# Item.net
KiCad netlist of a schematic drawn in Altium Designer
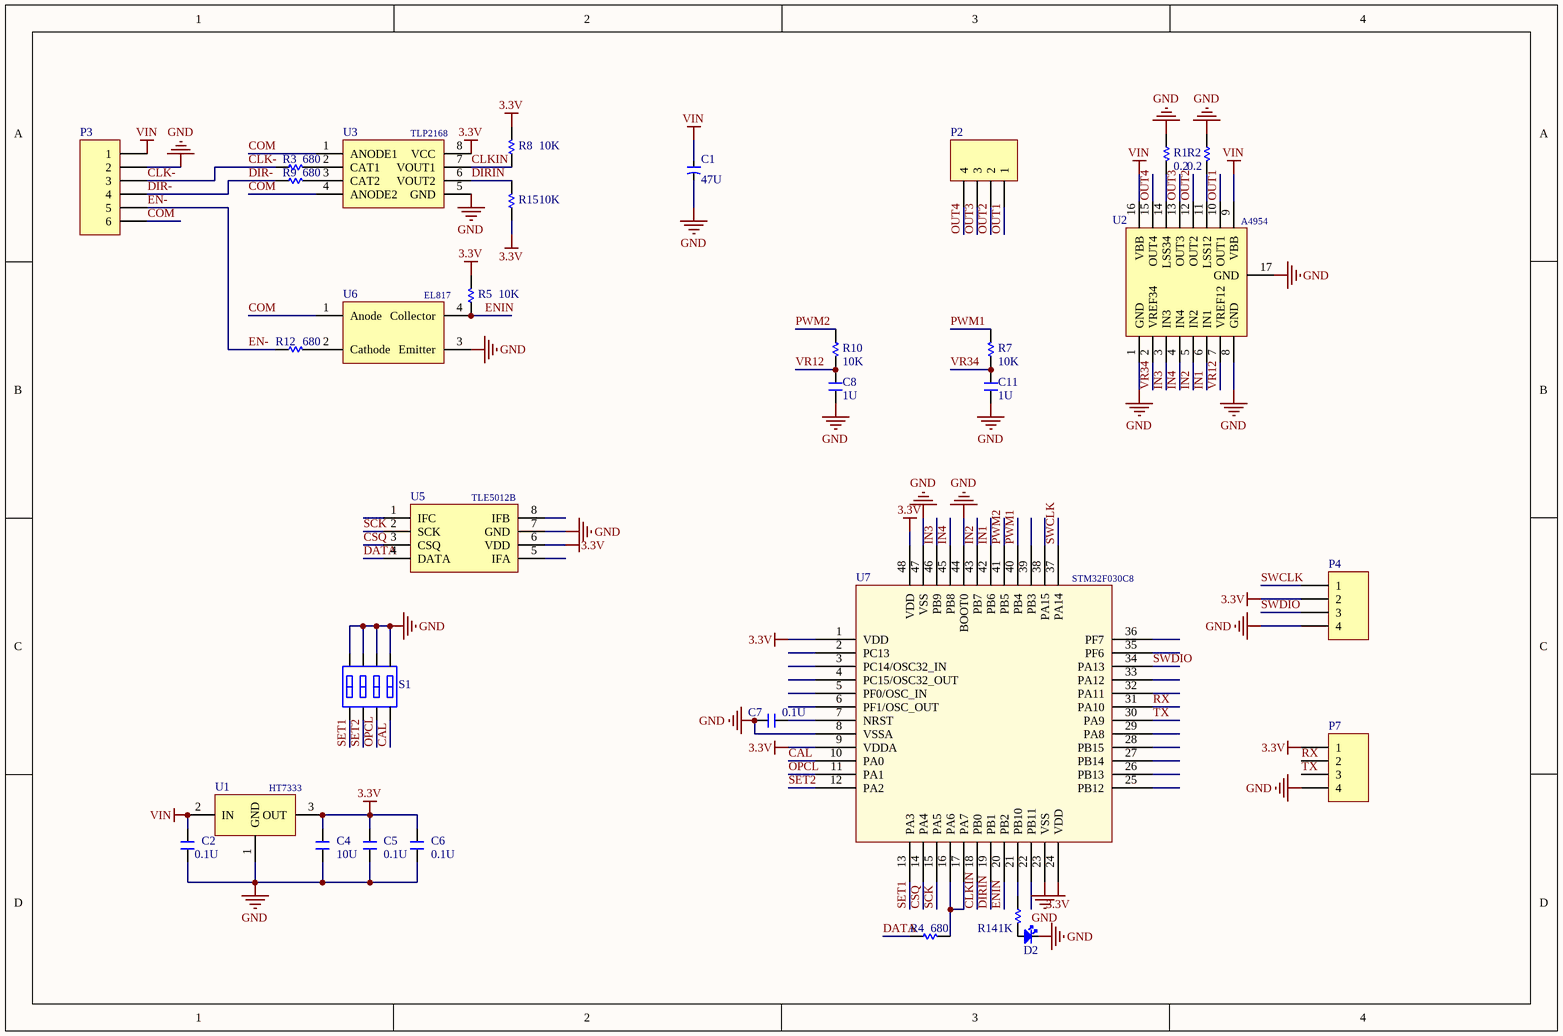
[diagram p0: Item.SchDoc]

(export (version "E")
  (design (tool "Eeschema 10.0.6"))
  (components
    (comp (ref "C1")
      (value "47U")
      (footprint "CAP6377")
      (description "Polarized Capacitor (Axial)")
      (fields (field (name "Comment") "CAP POL") (field (name "PUBLISHER") "Altium Limited"))
      (libsource (lib "MySchib") (part "CAP POL"))
    )
    (comp (ref "C2")
      (value "0.1U")
      (footprint "0805")
      (description "Capacitor")
      (fields (field (name "Comment") "CAP") (field (name "PUBLISHER") "Altium Limited"))
      (libsource (lib "MySchib") (part "CAP"))
    )
    (comp (ref "C4")
      (value "10U")
      (footprint "0805")
      (description "Capacitor")
      (fields (field (name "Comment") "CAP") (field (name "PUBLISHER") "Altium Limited"))
      (libsource (lib "MySchib") (part "CAP"))
    )
    (comp (ref "C5")
      (value "0.1U")
      (footprint "0805")
      (description "Capacitor")
      (fields (field (name "Comment") "CAP") (field (name "PUBLISHER") "Altium Limited"))
      (libsource (lib "MySchib") (part "CAP"))
    )
    (comp (ref "C6")
      (value "0.1U")
      (footprint "0805")
      (description "Capacitor")
      (fields (field (name "Comment") "CAP") (field (name "PUBLISHER") "Altium Limited"))
      (libsource (lib "MySchib") (part "CAP"))
    )
    (comp (ref "C7")
      (value "0.1U")
      (footprint "0805")
      (description "Capacitor")
      (fields (field (name "Comment") "CAP") (field (name "PUBLISHER") "Altium Limited"))
      (libsource (lib "MySchib") (part "CAP"))
    )
    (comp (ref "C8")
      (value "1U")
      (footprint "0805")
      (description "Capacitor")
      (fields (field (name "Comment") "CAP") (field (name "PUBLISHER") "Altium Limited"))
      (libsource (lib "MySchib") (part "CAP"))
    )
    (comp (ref "C11")
      (value "1U")
      (footprint "0805")
      (description "Capacitor")
      (fields (field (name "Comment") "CAP") (field (name "PUBLISHER") "Altium Limited"))
      (libsource (lib "MySchib") (part "CAP"))
    )
    (comp (ref "D2")
      (value "LED")
      (footprint "0805")
      (description "Typical INFRARED GaAs LED")
      (fields (field (name "PUBLISHER") "Altium Limited"))
      (libsource (lib "MySchib") (part "LED"))
    )
    (comp (ref "P2")
      (value "HEADER4")
      (footprint "XH-4")
      (description "Header, 4-Pin")
      (fields (field (name "PUBLISHER") "Altium Limited"))
      (libsource (lib "MySchib") (part "HEADER4"))
    )
    (comp (ref "P3")
      (value "HEADER6")
      (footprint "XH-6")
      (description "Header, 6-Pin")
      (fields (field (name "PUBLISHER") "Altium Limited"))
      (libsource (lib "MySchib") (part "HEADER6"))
    )
    (comp (ref "P4")
      (value "HEADER4")
      (footprint "4P-1.27MM")
      (description "Header, 4-Pin")
      (fields (field (name "PUBLISHER") "Altium Limited"))
      (libsource (lib "MySchib") (part "HEADER4"))
    )
    (comp (ref "P7")
      (value "HEADER4")
      (footprint "4P-1.27MM")
      (description "Header, 4-Pin")
      (fields (field (name "PUBLISHER") "Altium Limited"))
      (libsource (lib "MySchib") (part "HEADER4"))
    )
    (comp (ref "R1")
      (value "0.2")
      (footprint "1206")
      (description "Resistor")
      (fields (field (name "Comment") "RES") (field (name "PUBLISHER") "Altium Limited"))
      (libsource (lib "MySchib") (part "RES"))
    )
    (comp (ref "R2")
      (value "0.2")
      (footprint "1206")
      (description "Resistor")
      (fields (field (name "Comment") "RES") (field (name "PUBLISHER") "Altium Limited"))
      (libsource (lib "MySchib") (part "RES"))
    )
    (comp (ref "R3")
      (value "680")
      (footprint "0805")
      (description "Resistor")
      (fields (field (name "Comment") "RES") (field (name "PUBLISHER") "Altium Limited"))
      (libsource (lib "MySchib") (part "RES"))
    )
    (comp (ref "R4")
      (value "680")
      (footprint "0805")
      (description "Resistor")
      (fields (field (name "Comment") "RES") (field (name "PUBLISHER") "Altium Limited"))
      (libsource (lib "MySchib") (part "RES"))
    )
    (comp (ref "R5")
      (value "10K")
      (footprint "0805")
      (description "Resistor")
      (fields (field (name "Comment") "RES") (field (name "PUBLISHER") "Altium Limited"))
      (libsource (lib "MySchib") (part "RES"))
    )
    (comp (ref "R7")
      (value "10K")
      (footprint "0805")
      (description "Resistor")
      (fields (field (name "Comment") "RES") (field (name "PUBLISHER") "Altium Limited"))
      (libsource (lib "MySchib") (part "RES"))
    )
    (comp (ref "R8")
      (value "10K")
      (footprint "0805")
      (description "Resistor")
      (fields (field (name "Comment") "RES") (field (name "PUBLISHER") "Altium Limited"))
      (libsource (lib "MySchib") (part "RES"))
    )
    (comp (ref "R9")
      (value "680")
      (footprint "0805")
      (description "Resistor")
      (fields (field (name "Comment") "RES") (field (name "PUBLISHER") "Altium Limited"))
      (libsource (lib "MySchib") (part "RES"))
    )
    (comp (ref "R10")
      (value "10K")
      (footprint "0805")
      (description "Resistor")
      (fields (field (name "Comment") "RES") (field (name "PUBLISHER") "Altium Limited"))
      (libsource (lib "MySchib") (part "RES"))
    )
    (comp (ref "R12")
      (value "680")
      (footprint "0805")
      (description "Resistor")
      (fields (field (name "Comment") "RES") (field (name "PUBLISHER") "Altium Limited"))
      (libsource (lib "MySchib") (part "RES"))
    )
    (comp (ref "R14")
      (value "1K")
      (footprint "0805")
      (description "Resistor")
      (fields (field (name "Comment") "RES") (field (name "PUBLISHER") "Altium Limited"))
      (libsource (lib "MySchib") (part "RES"))
    )
    (comp (ref "R15")
      (value "10K")
      (footprint "0805")
      (description "Resistor")
      (fields (field (name "Comment") "RES") (field (name "PUBLISHER") "Altium Limited"))
      (libsource (lib "MySchib") (part "RES"))
    )
    (comp (ref "S1")
      (value "SWDIP-4")
      (footprint "SWDIP-4")
      (description "DIP Switch, 4Position, SPST")
      (fields (field (name "PUBLISHER") "Altium Limited"))
      (libsource (lib "MySchib") (part "SWDIP-4"))
    )
    (comp (ref "U1")
      (value "HT7333")
      (footprint "SOT89")
      (description "Positive Voltage Regulator")
      (fields (field (name "PUBLISHER") "Altium Limited"))
      (libsource (lib "MySchib") (part "HT7333"))
    )
    (comp (ref "U2")
      (value "A4954")
      (footprint "TSSOP16-A4954")
      (description "Dual Full-Bridge  DMOS PWM Motor Driver")
      (libsource (lib "MySchib") (part "A4954"))
    )
    (comp (ref "U3")
      (value "TLP2168")
      (footprint "SO-8_3.9mm")
      (description "HIGH SPEED 10MBit/s LOGIC GATE  PHOTOCOUPLER")
      (libsource (lib "MySchib") (part "TLP2168"))
    )
    (comp (ref "U5")
      (value "TLE5012B")
      (footprint "PG-DSO-8F")
      (description "GMR-Based Angle Sensor")
      (libsource (lib "MySchib") (part "TLE5012B"))
    )
    (comp (ref "U6")
      (value "EL817")
      (footprint "SOP-4_P2.54")
      (description "4 PIN PHOTOTRANSISTOR")
      (libsource (lib "MySchib") (part "EL817"))
    )
    (comp (ref "U7")
      (value "STM32F030C8")
      (footprint "LQFP-48_7x7x05P")
      (description "ST Microcontroller")
      (libsource (lib "MySchib") (part "STM32F030C8"))
    )
  )
  (nets
    (net (code "1") (name "/CAL") (class "Default")
      (node (ref "S1") (pin "7") (pinfunction "A4_7") (pintype "passive"))
      (node (ref "U7") (pin "10") (pinfunction "PA0_10") (pintype "passive"))
    )
    (net (code "2") (name "/CLK-") (class "Default")
      (node (ref "P3") (pin "3") (pinfunction "3_3") (pintype "passive"))
      (node (ref "R3") (pin "1") (pinfunction "1_1") (pintype "passive"))
    )
    (net (code "3") (name "/CLKIN") (class "Default")
      (node (ref "R8") (pin "1") (pinfunction "1_1") (pintype "passive"))
      (node (ref "U3") (pin "7") (pinfunction "VOUT1_7") (pintype "passive"))
      (node (ref "U7") (pin "18") (pinfunction "PB0_18") (pintype "passive"))
    )
    (net (code "4") (name "/COM") (class "Default")
      (node (ref "P3") (pin "6") (pinfunction "6_6") (pintype "passive"))
      (node (ref "U3") (pin "1") (pinfunction "ANODE1_1") (pintype "passive"))
      (node (ref "U3") (pin "4") (pinfunction "ANODE2_4") (pintype "passive"))
      (node (ref "U6") (pin "1") (pinfunction "Anode_1") (pintype "passive"))
    )
    (net (code "5") (name "/CSQ") (class "Default")
      (node (ref "U5") (pin "3") (pinfunction "CSQ_3") (pintype "passive"))
      (node (ref "U7") (pin "14") (pinfunction "PA4_14") (pintype "passive"))
    )
    (net (code "6") (name "/DATA") (class "Default")
      (node (ref "R4") (pin "1") (pinfunction "1_1") (pintype "passive"))
      (node (ref "U5") (pin "4") (pinfunction "DATA_4") (pintype "passive"))
    )
    (net (code "7") (name "/DIR-") (class "Default")
      (node (ref "P3") (pin "4") (pinfunction "4_4") (pintype "passive"))
      (node (ref "R9") (pin "1") (pinfunction "1_1") (pintype "passive"))
    )
    (net (code "8") (name "/DIRIN") (class "Default")
      (node (ref "R15") (pin "2") (pinfunction "2_2") (pintype "passive"))
      (node (ref "U3") (pin "6") (pinfunction "VOUT2_6") (pintype "passive"))
      (node (ref "U7") (pin "19") (pinfunction "PB1_19") (pintype "passive"))
    )
    (net (code "9") (name "/EN-") (class "Default")
      (node (ref "P3") (pin "5") (pinfunction "5_5") (pintype "passive"))
      (node (ref "R12") (pin "1") (pinfunction "1_1") (pintype "passive"))
    )
    (net (code "10") (name "/ENIN") (class "Default")
      (node (ref "R5") (pin "1") (pinfunction "1_1") (pintype "passive"))
      (node (ref "U6") (pin "4") (pinfunction "Collector_4") (pintype "passive"))
      (node (ref "U7") (pin "20") (pinfunction "PB2_20") (pintype "passive"))
    )
    (net (code "11") (name "/IN1") (class "Default")
      (node (ref "U2") (pin "6") (pinfunction "IN1_6") (pintype "passive"))
      (node (ref "U7") (pin "42") (pinfunction "PB6_42") (pintype "passive"))
    )
    (net (code "12") (name "/IN2") (class "Default")
      (node (ref "U2") (pin "5") (pinfunction "IN2_5") (pintype "passive"))
      (node (ref "U7") (pin "43") (pinfunction "PB7_43") (pintype "passive"))
    )
    (net (code "13") (name "/IN3") (class "Default")
      (node (ref "U2") (pin "3") (pinfunction "IN3_3") (pintype "passive"))
      (node (ref "U7") (pin "46") (pinfunction "PB9_46") (pintype "passive"))
    )
    (net (code "14") (name "/IN4") (class "Default")
      (node (ref "U2") (pin "4") (pinfunction "IN4_4") (pintype "passive"))
      (node (ref "U7") (pin "45") (pinfunction "PB8_45") (pintype "passive"))
    )
    (net (code "15") (name "/OPCL") (class "Default")
      (node (ref "S1") (pin "5") (pinfunction "A3_5") (pintype "passive"))
      (node (ref "U7") (pin "11") (pinfunction "PA1_11") (pintype "passive"))
    )
    (net (code "16") (name "/OUT1") (class "Default")
      (node (ref "P2") (pin "1") (pinfunction "1_1") (pintype "passive"))
      (node (ref "U2") (pin "10") (pinfunction "OUT1_10") (pintype "passive"))
    )
    (net (code "17") (name "/OUT2") (class "Default")
      (node (ref "P2") (pin "2") (pinfunction "2_2") (pintype "passive"))
      (node (ref "U2") (pin "12") (pinfunction "OUT2_12") (pintype "passive"))
    )
    (net (code "18") (name "/OUT3") (class "Default")
      (node (ref "P2") (pin "3") (pinfunction "3_3") (pintype "passive"))
      (node (ref "U2") (pin "13") (pinfunction "OUT3_13") (pintype "passive"))
    )
    (net (code "19") (name "/OUT4") (class "Default")
      (node (ref "P2") (pin "4") (pinfunction "4_4") (pintype "passive"))
      (node (ref "U2") (pin "15") (pinfunction "OUT4_15") (pintype "passive"))
    )
    (net (code "20") (name "/PWM1") (class "Default")
      (node (ref "R7") (pin "2") (pinfunction "2_2") (pintype "passive"))
      (node (ref "U7") (pin "40") (pinfunction "PB4_40") (pintype "passive"))
    )
    (net (code "21") (name "/PWM2") (class "Default")
      (node (ref "R10") (pin "1") (pinfunction "1_1") (pintype "passive"))
      (node (ref "U7") (pin "41") (pinfunction "PB5_41") (pintype "passive"))
    )
    (net (code "22") (name "/RX") (class "Default")
      (node (ref "P7") (pin "2") (pinfunction "2_2") (pintype "passive"))
      (node (ref "U7") (pin "31") (pinfunction "PA10_31") (pintype "passive"))
    )
    (net (code "23") (name "/SCK") (class "Default")
      (node (ref "U5") (pin "2") (pinfunction "SCK_2") (pintype "passive"))
      (node (ref "U7") (pin "15") (pinfunction "PA5_15") (pintype "passive"))
    )
    (net (code "24") (name "/SET1") (class "Default")
      (node (ref "S1") (pin "1") (pinfunction "A1_1") (pintype "passive"))
      (node (ref "U7") (pin "13") (pinfunction "PA3_13") (pintype "passive"))
    )
    (net (code "25") (name "/SET2") (class "Default")
      (node (ref "S1") (pin "3") (pinfunction "A2_3") (pintype "passive"))
      (node (ref "U7") (pin "12") (pinfunction "PA2_12") (pintype "passive"))
    )
    (net (code "26") (name "/SWCLK") (class "Default")
      (node (ref "P4") (pin "1") (pinfunction "1_1") (pintype "passive"))
      (node (ref "U7") (pin "37") (pinfunction "PA14_37") (pintype "passive"))
    )
    (net (code "27") (name "/SWDIO") (class "Default")
      (node (ref "P4") (pin "3") (pinfunction "3_3") (pintype "passive"))
      (node (ref "U7") (pin "34") (pinfunction "PA13_34") (pintype "passive"))
    )
    (net (code "28") (name "/TX") (class "Default")
      (node (ref "P7") (pin "3") (pinfunction "3_3") (pintype "passive"))
      (node (ref "U7") (pin "30") (pinfunction "PA9_30") (pintype "passive"))
    )
    (net (code "29") (name "/VR12") (class "Default")
      (node (ref "C8") (pin "1") (pinfunction "1_1") (pintype "passive"))
      (node (ref "R10") (pin "2") (pinfunction "2_2") (pintype "passive"))
      (node (ref "U2") (pin "7") (pinfunction "VREF12_7") (pintype "passive"))
    )
    (net (code "30") (name "/VR34") (class "Default")
      (node (ref "C11") (pin "1") (pinfunction "1_1") (pintype "passive"))
      (node (ref "R7") (pin "1") (pinfunction "1_1") (pintype "passive"))
      (node (ref "U2") (pin "2") (pinfunction "VREF34_2") (pintype "passive"))
    )
    (net (code "31") (name "3.3V") (class "Default")
      (node (ref "C4") (pin "1") (pinfunction "1_1") (pintype "passive"))
      (node (ref "C5") (pin "1") (pinfunction "1_1") (pintype "passive"))
      (node (ref "C6") (pin "1") (pinfunction "1_1") (pintype "passive"))
      (node (ref "P4") (pin "2") (pinfunction "2_2") (pintype "passive"))
      (node (ref "P7") (pin "1") (pinfunction "1_1") (pintype "passive"))
      (node (ref "R15") (pin "1") (pinfunction "1_1") (pintype "passive"))
      (node (ref "R5") (pin "2") (pinfunction "2_2") (pintype "passive"))
      (node (ref "R8") (pin "2") (pinfunction "2_2") (pintype "passive"))
      (node (ref "U1") (pin "3") (pinfunction "OUT_3") (pintype "power_in"))
      (node (ref "U3") (pin "8") (pinfunction "VCC_8") (pintype "passive"))
      (node (ref "U5") (pin "6") (pinfunction "VDD_6") (pintype "passive"))
      (node (ref "U7") (pin "1") (pinfunction "VDD_1") (pintype "passive"))
      (node (ref "U7") (pin "24") (pinfunction "VDD_24") (pintype "passive"))
      (node (ref "U7") (pin "48") (pinfunction "VDD_48") (pintype "passive"))
      (node (ref "U7") (pin "9") (pinfunction "VDDA_9") (pintype "passive"))
    )
    (net (code "32") (name "GND") (class "Default")
      (node (ref "C1") (pin "2") (pinfunction "2_2") (pintype "passive"))
      (node (ref "C11") (pin "2") (pinfunction "2_2") (pintype "passive"))
      (node (ref "C2") (pin "2") (pinfunction "2_2") (pintype "passive"))
      (node (ref "C4") (pin "2") (pinfunction "2_2") (pintype "passive"))
      (node (ref "C5") (pin "2") (pinfunction "2_2") (pintype "passive"))
      (node (ref "C6") (pin "2") (pinfunction "2_2") (pintype "passive"))
      (node (ref "C7") (pin "1") (pinfunction "1_1") (pintype "passive"))
      (node (ref "C8") (pin "2") (pinfunction "2_2") (pintype "passive"))
      (node (ref "D2") (pin "2") (pinfunction "K_2") (pintype "passive"))
      (node (ref "P3") (pin "2") (pinfunction "2_2") (pintype "passive"))
      (node (ref "P4") (pin "4") (pinfunction "4_4") (pintype "passive"))
      (node (ref "P7") (pin "4") (pinfunction "4_4") (pintype "passive"))
      (node (ref "R1") (pin "1") (pinfunction "1_1") (pintype "passive"))
      (node (ref "R2") (pin "1") (pinfunction "1_1") (pintype "passive"))
      (node (ref "S1") (pin "2") (pinfunction "B1_2") (pintype "passive"))
      (node (ref "S1") (pin "4") (pinfunction "B2_4") (pintype "passive"))
      (node (ref "S1") (pin "6") (pinfunction "B3_6") (pintype "passive"))
      (node (ref "S1") (pin "8") (pinfunction "B4_8") (pintype "passive"))
      (node (ref "U1") (pin "1") (pinfunction "GND_1") (pintype "power_in"))
      (node (ref "U2") (pin "1") (pinfunction "GND_1") (pintype "passive"))
      (node (ref "U2") (pin "17") (pinfunction "GND_17") (pintype "passive"))
      (node (ref "U2") (pin "8") (pinfunction "GND_8") (pintype "passive"))
      (node (ref "U3") (pin "5") (pinfunction "GND_5") (pintype "passive"))
      (node (ref "U5") (pin "7") (pinfunction "GND_7") (pintype "passive"))
      (node (ref "U6") (pin "3") (pinfunction "Emitter_3") (pintype "passive"))
      (node (ref "U7") (pin "23") (pinfunction "VSS_23") (pintype "passive"))
      (node (ref "U7") (pin "44") (pinfunction "BOOT0_44") (pintype "passive"))
      (node (ref "U7") (pin "47") (pinfunction "VSS_47") (pintype "passive"))
      (node (ref "U7") (pin "8") (pinfunction "VSSA_8") (pintype "passive"))
    )
    (net (code "33") (name "Net-(D2-A)") (class "Default")
      (node (ref "D2") (pin "1") (pinfunction "A_1") (pintype "passive"))
      (node (ref "R14") (pin "2") (pinfunction "2_2") (pintype "passive"))
    )
    (net (code "34") (name "Net-(U2-LSS12)") (class "Default")
      (node (ref "R2") (pin "2") (pinfunction "2_2") (pintype "passive"))
      (node (ref "U2") (pin "11") (pinfunction "LSS12_11") (pintype "passive"))
    )
    (net (code "35") (name "Net-(U2-LSS34)") (class "Default")
      (node (ref "R1") (pin "2") (pinfunction "2_2") (pintype "passive"))
      (node (ref "U2") (pin "14") (pinfunction "LSS34_14") (pintype "passive"))
    )
    (net (code "36") (name "Net-(U3-CAT1)") (class "Default")
      (node (ref "R3") (pin "2") (pinfunction "2_2") (pintype "passive"))
      (node (ref "U3") (pin "2") (pinfunction "CAT1_2") (pintype "passive"))
    )
    (net (code "37") (name "Net-(U3-CAT2)") (class "Default")
      (node (ref "R9") (pin "2") (pinfunction "2_2") (pintype "passive"))
      (node (ref "U3") (pin "3") (pinfunction "CAT2_3") (pintype "passive"))
    )
    (net (code "38") (name "Net-(U6-Cathode)") (class "Default")
      (node (ref "R12") (pin "2") (pinfunction "2_2") (pintype "passive"))
      (node (ref "U6") (pin "2") (pinfunction "Cathode_2") (pintype "passive"))
    )
    (net (code "39") (name "Net-(U7-NRST)") (class "Default")
      (node (ref "C7") (pin "2") (pinfunction "2_2") (pintype "passive"))
      (node (ref "U7") (pin "7") (pinfunction "NRST_7") (pintype "passive"))
    )
    (net (code "40") (name "Net-(U7-PA6)") (class "Default")
      (node (ref "R4") (pin "2") (pinfunction "2_2") (pintype "passive"))
      (node (ref "U7") (pin "16") (pinfunction "PA6_16") (pintype "passive"))
      (node (ref "U7") (pin "17") (pinfunction "PA7_17") (pintype "passive"))
    )
    (net (code "41") (name "Net-(U7-PB10)") (class "Default")
      (node (ref "R14") (pin "1") (pinfunction "1_1") (pintype "passive"))
      (node (ref "U7") (pin "21") (pinfunction "PB10_21") (pintype "passive"))
    )
    (net (code "42") (name "VIN") (class "Default")
      (node (ref "C1") (pin "1") (pinfunction "1_1") (pintype "passive"))
      (node (ref "C2") (pin "1") (pinfunction "1_1") (pintype "passive"))
      (node (ref "P3") (pin "1") (pinfunction "1_1") (pintype "passive"))
      (node (ref "U1") (pin "2") (pinfunction "IN_2") (pintype "power_in"))
      (node (ref "U2") (pin "16") (pinfunction "VBB_16") (pintype "passive"))
      (node (ref "U2") (pin "9") (pinfunction "VBB_9") (pintype "passive"))
    )
    (net (code "43") (name "unconnected-(U5-IFA-Pad5)") (class "Default")
      (node (ref "U5") (pin "5") (pinfunction "IFA_5") (pintype "passive"))
    )
    (net (code "44") (name "unconnected-(U5-IFB-Pad8)") (class "Default")
      (node (ref "U5") (pin "8") (pinfunction "IFB_8") (pintype "passive"))
    )
    (net (code "45") (name "unconnected-(U5-IFC-Pad1)") (class "Default")
      (node (ref "U5") (pin "1") (pinfunction "IFC_1") (pintype "passive"))
    )
    (net (code "46") (name "unconnected-(U7-PA8-Pad29)") (class "Default")
      (node (ref "U7") (pin "29") (pinfunction "PA8_29") (pintype "passive"))
    )
    (net (code "47") (name "unconnected-(U7-PA11-Pad32)") (class "Default")
      (node (ref "U7") (pin "32") (pinfunction "PA11_32") (pintype "passive"))
    )
    (net (code "48") (name "unconnected-(U7-PA12-Pad33)") (class "Default")
      (node (ref "U7") (pin "33") (pinfunction "PA12_33") (pintype "passive"))
    )
    (net (code "49") (name "unconnected-(U7-PA15-Pad38)") (class "Default")
      (node (ref "U7") (pin "38") (pinfunction "PA15_38") (pintype "passive"))
    )
    (net (code "50") (name "unconnected-(U7-PB3-Pad39)") (class "Default")
      (node (ref "U7") (pin "39") (pinfunction "PB3_39") (pintype "passive"))
    )
    (net (code "51") (name "unconnected-(U7-PB11-Pad22)") (class "Default")
      (node (ref "U7") (pin "22") (pinfunction "PB11_22") (pintype "passive"))
    )
    (net (code "52") (name "unconnected-(U7-PB12-Pad25)") (class "Default")
      (node (ref "U7") (pin "25") (pinfunction "PB12_25") (pintype "passive"))
    )
    (net (code "53") (name "unconnected-(U7-PB13-Pad26)") (class "Default")
      (node (ref "U7") (pin "26") (pinfunction "PB13_26") (pintype "passive"))
    )
    (net (code "54") (name "unconnected-(U7-PB14-Pad27)") (class "Default")
      (node (ref "U7") (pin "27") (pinfunction "PB14_27") (pintype "passive"))
    )
    (net (code "55") (name "unconnected-(U7-PB15-Pad28)") (class "Default")
      (node (ref "U7") (pin "28") (pinfunction "PB15_28") (pintype "passive"))
    )
    (net (code "56") (name "unconnected-(U7-PC13-Pad2)") (class "Default")
      (node (ref "U7") (pin "2") (pinfunction "PC13_2") (pintype "passive"))
    )
    (net (code "57") (name "unconnected-(U7-PC14{slash}OSC32_IN-Pad3)") (class "Default")
      (node (ref "U7") (pin "3") (pinfunction "PC14/OSC32_IN_3") (pintype "passive"))
    )
    (net (code "58") (name "unconnected-(U7-PC15{slash}OSC32_OUT-Pad4)") (class "Default")
      (node (ref "U7") (pin "4") (pinfunction "PC15/OSC32_OUT_4") (pintype "power_in"))
    )
    (net (code "59") (name "unconnected-(U7-PF0{slash}OSC_IN-Pad5)") (class "Default")
      (node (ref "U7") (pin "5") (pinfunction "PF0/OSC_IN_5") (pintype "power_in"))
    )
    (net (code "60") (name "unconnected-(U7-PF1{slash}OSC_OUT-Pad6)") (class "Default")
      (node (ref "U7") (pin "6") (pinfunction "PF1/OSC_OUT_6") (pintype "power_in"))
    )
    (net (code "61") (name "unconnected-(U7-PF6-Pad35)") (class "Default")
      (node (ref "U7") (pin "35") (pinfunction "PF6_35") (pintype "passive"))
    )
    (net (code "62") (name "unconnected-(U7-PF7-Pad36)") (class "Default")
      (node (ref "U7") (pin "36") (pinfunction "PF7_36") (pintype "passive"))
    )
  )
)
